# LEMNOS3.net
KiCad netlist of a schematic drawn in EAGLE
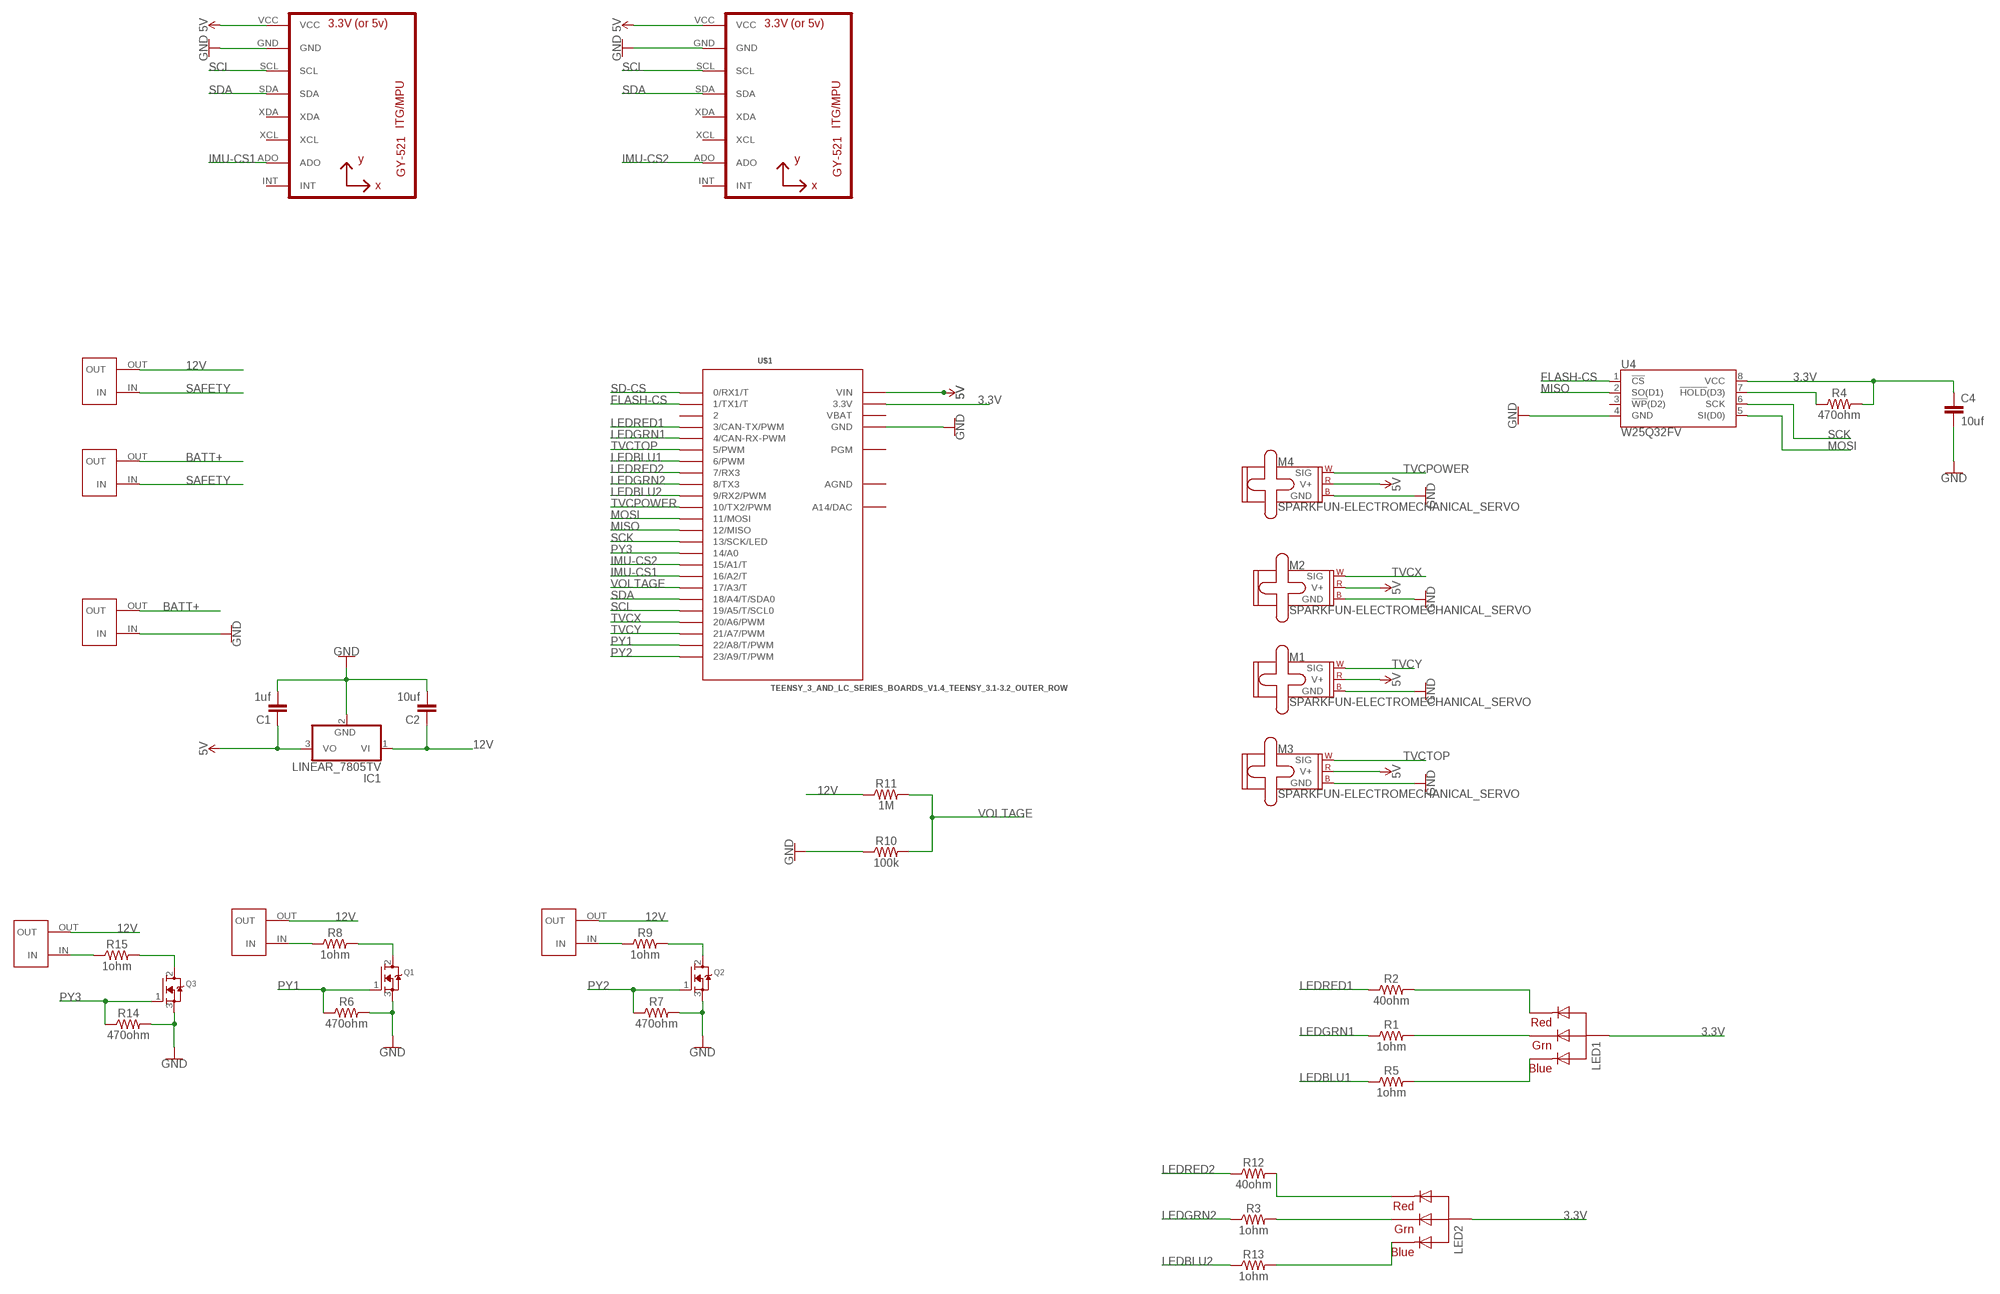
[diagram p0: schematic, sheet 1]

(export (version "E")
  (design (tool "Eeschema 10.0.6"))
  (components
    (comp (ref "C1")
      (value "1uf")
      (footprint "eagle-import:SPARKFUN-CAPACITORS_CAP-PTH-2.54")
      (libsource (lib "eagle-import") (part "SPARKFUN-CAPACITORS_22PF-PTH-2.54MM-200V-5%"))
    )
    (comp (ref "C2")
      (value "10uf")
      (footprint "eagle-import:SPARKFUN-CAPACITORS_CAP-PTH-2.54")
      (libsource (lib "eagle-import") (part "SPARKFUN-CAPACITORS_22PF-PTH-2.54MM-200V-5%"))
    )
    (comp (ref "C4")
      (value "10uf")
      (footprint "eagle-import:SPARKFUN-CAPACITORS_CAP-PTH-2.54")
      (libsource (lib "eagle-import") (part "SPARKFUN-CAPACITORS_22PF-PTH-2.54MM-200V-5%"))
    )
    (comp (ref "IC1")
      (value "LINEAR_7805TV")
      (footprint "eagle-import:LINEAR_TO220V")
      (libsource (lib "eagle-import") (part "LINEAR_78TV05"))
    )
    (comp (ref "LED1")
      (value "RGBLED_CA-5MM")
      (footprint "eagle-import:LED5MMRGB")
      (libsource (lib "eagle-import") (part "RGBLED_CA-5MM"))
    )
    (comp (ref "LED2")
      (value "RGBLED_CA-5MM")
      (footprint "eagle-import:LED5MMRGB")
      (libsource (lib "eagle-import") (part "RGBLED_CA-5MM"))
    )
    (comp (ref "M1")
      (value "SPARKFUN-ELECTROMECHANICAL_SERVO")
      (footprint "eagle-import:SPARKFUN-ELECTROMECHANICAL_1X03")
      (libsource (lib "eagle-import") (part "SPARKFUN-ELECTROMECHANICAL_SERVO"))
    )
    (comp (ref "M2")
      (value "SPARKFUN-ELECTROMECHANICAL_SERVO")
      (footprint "eagle-import:SPARKFUN-ELECTROMECHANICAL_1X03")
      (libsource (lib "eagle-import") (part "SPARKFUN-ELECTROMECHANICAL_SERVO"))
    )
    (comp (ref "M3")
      (value "SPARKFUN-ELECTROMECHANICAL_SERVO")
      (footprint "eagle-import:SPARKFUN-ELECTROMECHANICAL_1X03")
      (libsource (lib "eagle-import") (part "SPARKFUN-ELECTROMECHANICAL_SERVO"))
    )
    (comp (ref "M4")
      (value "SPARKFUN-ELECTROMECHANICAL_SERVO")
      (footprint "eagle-import:SPARKFUN-ELECTROMECHANICAL_1X03")
      (libsource (lib "eagle-import") (part "SPARKFUN-ELECTROMECHANICAL_SERVO"))
    )
    (comp (ref "Q1")
      (value "ADAFRUIT_MOSFET-NGDS_TO220V")
      (footprint "eagle-import:ADAFRUIT_TO220V")
      (libsource (lib "eagle-import") (part "ADAFRUIT_MOSFET-NGDS_TO220V"))
    )
    (comp (ref "Q2")
      (value "ADAFRUIT_MOSFET-NGDS_TO220V")
      (footprint "eagle-import:ADAFRUIT_TO220V")
      (libsource (lib "eagle-import") (part "ADAFRUIT_MOSFET-NGDS_TO220V"))
    )
    (comp (ref "Q3")
      (value "ADAFRUIT_MOSFET-NGDS_TO220V")
      (footprint "eagle-import:ADAFRUIT_TO220V")
      (libsource (lib "eagle-import") (part "ADAFRUIT_MOSFET-NGDS_TO220V"))
    )
    (comp (ref "R1")
      (value "1ohm")
      (footprint "eagle-import:SPARKFUN-RESISTORS_AXIAL-0.3")
      (libsource (lib "eagle-import") (part "SPARKFUN-RESISTORS_10MOHM-HORIZ-1/4W-5%"))
    )
    (comp (ref "R2")
      (value "40ohm")
      (footprint "eagle-import:SPARKFUN-RESISTORS_AXIAL-0.3")
      (libsource (lib "eagle-import") (part "SPARKFUN-RESISTORS_10MOHM-HORIZ-1/4W-5%"))
    )
    (comp (ref "R3")
      (value "1ohm")
      (footprint "eagle-import:SPARKFUN-RESISTORS_AXIAL-0.3")
      (libsource (lib "eagle-import") (part "SPARKFUN-RESISTORS_10MOHM-HORIZ-1/4W-5%"))
    )
    (comp (ref "R4")
      (value "470ohm")
      (footprint "eagle-import:SPARKFUN-RESISTORS_AXIAL-0.3")
      (libsource (lib "eagle-import") (part "SPARKFUN-RESISTORS_10MOHM-HORIZ-1/4W-5%"))
    )
    (comp (ref "R5")
      (value "1ohm")
      (footprint "eagle-import:SPARKFUN-RESISTORS_AXIAL-0.3")
      (libsource (lib "eagle-import") (part "SPARKFUN-RESISTORS_10MOHM-HORIZ-1/4W-5%"))
    )
    (comp (ref "R6")
      (value "470ohm")
      (footprint "eagle-import:SPARKFUN-RESISTORS_AXIAL-0.3")
      (libsource (lib "eagle-import") (part "SPARKFUN-RESISTORS_10MOHM-HORIZ-1/4W-5%"))
    )
    (comp (ref "R7")
      (value "470ohm")
      (footprint "eagle-import:SPARKFUN-RESISTORS_AXIAL-0.3")
      (libsource (lib "eagle-import") (part "SPARKFUN-RESISTORS_10MOHM-HORIZ-1/4W-5%"))
    )
    (comp (ref "R8")
      (value "1ohm")
      (footprint "eagle-import:SPARKFUN-RESISTORS_AXIAL-0.3")
      (libsource (lib "eagle-import") (part "SPARKFUN-RESISTORS_10MOHM-HORIZ-1/4W-5%"))
    )
    (comp (ref "R9")
      (value "1ohm")
      (footprint "eagle-import:SPARKFUN-RESISTORS_AXIAL-0.3")
      (libsource (lib "eagle-import") (part "SPARKFUN-RESISTORS_10MOHM-HORIZ-1/4W-5%"))
    )
    (comp (ref "R10")
      (value "100k")
      (footprint "eagle-import:SPARKFUN-RESISTORS_AXIAL-0.3")
      (libsource (lib "eagle-import") (part "SPARKFUN-RESISTORS_10MOHM-HORIZ-1/4W-5%"))
    )
    (comp (ref "R11")
      (value "1M")
      (footprint "eagle-import:SPARKFUN-RESISTORS_AXIAL-0.3")
      (libsource (lib "eagle-import") (part "SPARKFUN-RESISTORS_10MOHM-HORIZ-1/4W-5%"))
    )
    (comp (ref "R12")
      (value "40ohm")
      (footprint "eagle-import:SPARKFUN-RESISTORS_AXIAL-0.3")
      (libsource (lib "eagle-import") (part "SPARKFUN-RESISTORS_10MOHM-HORIZ-1/4W-5%"))
    )
    (comp (ref "R13")
      (value "1ohm")
      (footprint "eagle-import:SPARKFUN-RESISTORS_AXIAL-0.3")
      (libsource (lib "eagle-import") (part "SPARKFUN-RESISTORS_10MOHM-HORIZ-1/4W-5%"))
    )
    (comp (ref "R14")
      (value "470ohm")
      (footprint "eagle-import:SPARKFUN-RESISTORS_AXIAL-0.3")
      (libsource (lib "eagle-import") (part "SPARKFUN-RESISTORS_10MOHM-HORIZ-1/4W-5%"))
    )
    (comp (ref "R15")
      (value "1ohm")
      (footprint "eagle-import:SPARKFUN-RESISTORS_AXIAL-0.3")
      (libsource (lib "eagle-import") (part "SPARKFUN-RESISTORS_10MOHM-HORIZ-1/4W-5%"))
    )
    (comp (ref "U$1")
      (value "TEENSY_3_AND_LC_SERIES_BOARDS_V1.4_TEENSY_3.1-3.2_OUTER_ROW")
      (footprint "eagle-import:TEENSY_3_AND_LC_SERIES_BOARDS_V1.4_TEENSY_3.0-3.2&LC_OUTER_ROW")
      (libsource (lib "eagle-import") (part "TEENSY_3_AND_LC_SERIES_BOARDS_V1.4_TEENSY_3.1-3.2_OUTER_ROW"))
    )
    (comp (ref "U$2")
      (value "BLACKTERMBLOCK_BLACKTERMBLOCK")
      (footprint "eagle-import:BLACKTERMBLOCK_BLACKTERMBLOCK")
      (libsource (lib "eagle-import") (part "BLACKTERMBLOCK_BLACKTERMBLOCK"))
    )
    (comp (ref "U$3")
      (value "BLACKTERMBLOCK_BLACKTERMBLOCK")
      (footprint "eagle-import:BLACKTERMBLOCK_BLACKTERMBLOCK")
      (libsource (lib "eagle-import") (part "BLACKTERMBLOCK_BLACKTERMBLOCK"))
    )
    (comp (ref "U$4")
      (value "BLACKTERMBLOCK_BLACKTERMBLOCK")
      (footprint "eagle-import:BLACKTERMBLOCK_BLACKTERMBLOCK")
      (libsource (lib "eagle-import") (part "BLACKTERMBLOCK_BLACKTERMBLOCK"))
    )
    (comp (ref "U$5")
      (value "BLACKTERMBLOCK_BLACKTERMBLOCK")
      (footprint "eagle-import:BLACKTERMBLOCK_BLACKTERMBLOCK")
      (libsource (lib "eagle-import") (part "BLACKTERMBLOCK_BLACKTERMBLOCK"))
    )
    (comp (ref "U$6")
      (value "BLACKTERMBLOCK_BLACKTERMBLOCK")
      (footprint "eagle-import:BLACKTERMBLOCK_BLACKTERMBLOCK")
      (libsource (lib "eagle-import") (part "BLACKTERMBLOCK_BLACKTERMBLOCK"))
    )
    (comp (ref "U$8")
      (value "BLACKTERMBLOCK_BLACKTERMBLOCK")
      (footprint "eagle-import:BLACKTERMBLOCK_BLACKTERMBLOCK")
      (libsource (lib "eagle-import") (part "BLACKTERMBLOCK_BLACKTERMBLOCK"))
    )
    (comp (ref "U1")
      (value "GY-521_GY-521MPU6050")
      (footprint "eagle-import:GY-521_GY-521")
      (libsource (lib "eagle-import") (part "GY-521_GY-521MPU6050"))
    )
    (comp (ref "U2")
      (value "GY-521_GY-521MPU6050")
      (footprint "eagle-import:GY-521_GY-521")
      (libsource (lib "eagle-import") (part "GY-521_GY-521MPU6050"))
    )
    (comp (ref "U4")
      (value "W25Q32FV")
      (footprint "eagle-import:SPARKFUN-IC-MEMORY_SOIC-8")
      (libsource (lib "eagle-import") (part "SPARKFUN-IC-MEMORY_W25Q32FVSS"))
    )
  )
  (nets
    (net (code "1") (name "/3.3V") (class "Default")
      (node (ref "C4") (pin "1") (pinfunction "1_1") (pintype "passive"))
      (node (ref "LED1") (pin "2") (pinfunction "VCC_2") (pintype "bidirectional"))
      (node (ref "LED2") (pin "2") (pinfunction "VCC_2") (pintype "bidirectional"))
      (node (ref "R4") (pin "P$2") (pinfunction "2_P$2") (pintype "passive"))
      (node (ref "U$1") (pin "3.3V") (pinfunction "3.3V_3.3V") (pintype "power_in"))
      (node (ref "U$1") (pin "3.3V1") (pinfunction "3.3V_3.3V1") (pintype "power_in"))
      (node (ref "U4") (pin "8") (pinfunction "VCC_8") (pintype "bidirectional"))
    )
    (net (code "2") (name "/12V") (class "Default")
      (node (ref "C2") (pin "1") (pinfunction "1_1") (pintype "passive"))
      (node (ref "IC1") (pin "1") (pinfunction "VI_1") (pintype "input"))
      (node (ref "R11") (pin "P$1") (pinfunction "1_P$1") (pintype "passive"))
      (node (ref "U$2") (pin "OUT") (pinfunction "OUT_OUT") (pintype "bidirectional"))
      (node (ref "U$5") (pin "OUT") (pinfunction "OUT_OUT") (pintype "bidirectional"))
      (node (ref "U$6") (pin "OUT") (pinfunction "OUT_OUT") (pintype "bidirectional"))
      (node (ref "U$8") (pin "OUT") (pinfunction "OUT_OUT") (pintype "bidirectional"))
    )
    (net (code "3") (name "/AGND") (class "Default")
      (node (ref "U$1") (pin "AGND") (pinfunction "AGND_AGND") (pintype "power_in"))
    )
    (net (code "4") (name "/BATT+") (class "Default")
      (node (ref "U$3") (pin "OUT") (pinfunction "OUT_OUT") (pintype "bidirectional"))
      (node (ref "U$4") (pin "OUT") (pinfunction "OUT_OUT") (pintype "bidirectional"))
    )
    (net (code "5") (name "/FLASH-CS") (class "Default")
      (node (ref "U$1") (pin "1") (pinfunction "1/TX1/T_1") (pintype "bidirectional"))
      (node (ref "U4") (pin "1") (pinfunction "~{CS}_1") (pintype "bidirectional"))
    )
    (net (code "6") (name "/IMU-CS1") (class "Default")
      (node (ref "U$1") (pin "16/A2") (pinfunction "16/A2/T_16/A2") (pintype "bidirectional"))
      (node (ref "U1") (pin "ADO") (pinfunction "ADO_ADO") (pintype "bidirectional"))
    )
    (net (code "7") (name "/IMU-CS2") (class "Default")
      (node (ref "U$1") (pin "15/A1") (pinfunction "15/A1/T_15/A1") (pintype "bidirectional"))
      (node (ref "U2") (pin "ADO") (pinfunction "ADO_ADO") (pintype "bidirectional"))
    )
    (net (code "8") (name "/LEDBLU1") (class "Default")
      (node (ref "R5") (pin "P$1") (pinfunction "1_P$1") (pintype "passive"))
      (node (ref "U$1") (pin "6") (pinfunction "6/PWM_6") (pintype "bidirectional"))
    )
    (net (code "9") (name "/LEDBLU2") (class "Default")
      (node (ref "R13") (pin "P$1") (pinfunction "1_P$1") (pintype "passive"))
      (node (ref "U$1") (pin "9") (pinfunction "9/RX2/PWM_9") (pintype "bidirectional"))
    )
    (net (code "10") (name "/LEDGRN1") (class "Default")
      (node (ref "R1") (pin "P$1") (pinfunction "1_P$1") (pintype "passive"))
      (node (ref "U$1") (pin "4") (pinfunction "4/CAN-RX-PWM_4") (pintype "bidirectional"))
    )
    (net (code "11") (name "/LEDGRN2") (class "Default")
      (node (ref "R3") (pin "P$1") (pinfunction "1_P$1") (pintype "passive"))
      (node (ref "U$1") (pin "8") (pinfunction "8/TX3_8") (pintype "bidirectional"))
    )
    (net (code "12") (name "/LEDRED1") (class "Default")
      (node (ref "R2") (pin "P$1") (pinfunction "1_P$1") (pintype "passive"))
      (node (ref "U$1") (pin "3") (pinfunction "3/CAN-TX/PWM_3") (pintype "bidirectional"))
    )
    (net (code "13") (name "/LEDRED2") (class "Default")
      (node (ref "R12") (pin "P$1") (pinfunction "1_P$1") (pintype "passive"))
      (node (ref "U$1") (pin "7") (pinfunction "7/RX3_7") (pintype "bidirectional"))
    )
    (net (code "14") (name "/MISO") (class "Default")
      (node (ref "U$1") (pin "12") (pinfunction "12/MISO_12") (pintype "bidirectional"))
      (node (ref "U4") (pin "2") (pinfunction "SO(D1)_2") (pintype "bidirectional"))
    )
    (net (code "15") (name "/MOSI") (class "Default")
      (node (ref "U$1") (pin "11") (pinfunction "11/MOSI_11") (pintype "bidirectional"))
      (node (ref "U4") (pin "5") (pinfunction "SI(D0)_5") (pintype "bidirectional"))
    )
    (net (code "16") (name "/PY1") (class "Default")
      (node (ref "Q1") (pin "1") (pinfunction "G_1") (pintype "bidirectional"))
      (node (ref "R6") (pin "P$1") (pinfunction "1_P$1") (pintype "passive"))
      (node (ref "U$1") (pin "22/A8") (pinfunction "22/A8/T/PWM_22/A8") (pintype "bidirectional"))
    )
    (net (code "17") (name "/PY2") (class "Default")
      (node (ref "Q2") (pin "1") (pinfunction "G_1") (pintype "bidirectional"))
      (node (ref "R7") (pin "P$1") (pinfunction "1_P$1") (pintype "passive"))
      (node (ref "U$1") (pin "23/A9") (pinfunction "23/A9/T/PWM_23/A9") (pintype "bidirectional"))
    )
    (net (code "18") (name "/PY3") (class "Default")
      (node (ref "Q3") (pin "1") (pinfunction "G_1") (pintype "bidirectional"))
      (node (ref "R14") (pin "P$1") (pinfunction "1_P$1") (pintype "passive"))
      (node (ref "U$1") (pin "14/A0") (pinfunction "14/A0_14/A0") (pintype "bidirectional"))
    )
    (net (code "19") (name "/SAFETY") (class "Default")
      (node (ref "U$4") (pin "IN") (pinfunction "IN_IN") (pintype "bidirectional"))
      (node (ref "U$8") (pin "IN") (pinfunction "IN_IN") (pintype "bidirectional"))
    )
    (net (code "20") (name "/SCK") (class "Default")
      (node (ref "U$1") (pin "13") (pinfunction "13/SCK/LED_13") (pintype "bidirectional"))
      (node (ref "U4") (pin "6") (pinfunction "SCK_6") (pintype "bidirectional"))
    )
    (net (code "21") (name "/SCL") (class "Default")
      (node (ref "U$1") (pin "19/A5") (pinfunction "19/A5/T/SCL0_19/A5") (pintype "bidirectional"))
      (node (ref "U1") (pin "SCL") (pinfunction "SCL_SCL") (pintype "bidirectional"))
      (node (ref "U2") (pin "SCL") (pinfunction "SCL_SCL") (pintype "bidirectional"))
    )
    (net (code "22") (name "/SD-CS") (class "Default")
      (node (ref "U$1") (pin "0") (pinfunction "0/RX1/T_0") (pintype "bidirectional"))
    )
    (net (code "23") (name "/SDA") (class "Default")
      (node (ref "U$1") (pin "18/A4") (pinfunction "18/A4/T/SDA0_18/A4") (pintype "bidirectional"))
      (node (ref "U1") (pin "SDA") (pinfunction "SDA_SDA") (pintype "bidirectional"))
      (node (ref "U2") (pin "SDA") (pinfunction "SDA_SDA") (pintype "bidirectional"))
    )
    (net (code "24") (name "/TVCPOWER") (class "Default")
      (node (ref "M4") (pin "1") (pinfunction "SIG_1") (pintype "bidirectional"))
      (node (ref "U$1") (pin "10") (pinfunction "10/TX2/PWM_10") (pintype "bidirectional"))
    )
    (net (code "25") (name "/TVCTOP") (class "Default")
      (node (ref "M3") (pin "1") (pinfunction "SIG_1") (pintype "bidirectional"))
      (node (ref "U$1") (pin "5") (pinfunction "5/PWM_5") (pintype "bidirectional"))
    )
    (net (code "26") (name "/TVCX") (class "Default")
      (node (ref "M2") (pin "1") (pinfunction "SIG_1") (pintype "bidirectional"))
      (node (ref "U$1") (pin "20/A6") (pinfunction "20/A6/PWM_20/A6") (pintype "bidirectional"))
    )
    (net (code "27") (name "/TVCY") (class "Default")
      (node (ref "M1") (pin "1") (pinfunction "SIG_1") (pintype "bidirectional"))
      (node (ref "U$1") (pin "21/A7") (pinfunction "21/A7/PWM_21/A7") (pintype "bidirectional"))
    )
    (net (code "28") (name "/VBAT") (class "Default")
      (node (ref "U$1") (pin "VBAT") (pinfunction "VBAT_VBAT") (pintype "power_in"))
    )
    (net (code "29") (name "/VOLTAGE") (class "Default")
      (node (ref "R10") (pin "P$2") (pinfunction "2_P$2") (pintype "passive"))
      (node (ref "R11") (pin "P$2") (pinfunction "2_P$2") (pintype "passive"))
      (node (ref "U$1") (pin "17/A3") (pinfunction "17/A3/T_17/A3") (pintype "bidirectional"))
    )
    (net (code "30") (name "5V") (class "Default")
      (node (ref "C1") (pin "1") (pinfunction "1_1") (pintype "passive"))
      (node (ref "IC1") (pin "3") (pinfunction "VO_3") (pintype "passive"))
      (node (ref "M1") (pin "2") (pinfunction "V+_2") (pintype "bidirectional"))
      (node (ref "M2") (pin "2") (pinfunction "V+_2") (pintype "bidirectional"))
      (node (ref "M3") (pin "2") (pinfunction "V+_2") (pintype "bidirectional"))
      (node (ref "M4") (pin "2") (pinfunction "V+_2") (pintype "bidirectional"))
      (node (ref "U$1") (pin "VIN") (pinfunction "VIN_VIN") (pintype "power_in"))
      (node (ref "U1") (pin "VCC") (pinfunction "VCC_VCC") (pintype "bidirectional"))
      (node (ref "U2") (pin "VCC") (pinfunction "VCC_VCC") (pintype "bidirectional"))
    )
    (net (code "31") (name "GND") (class "Default")
      (node (ref "C1") (pin "2") (pinfunction "2_2") (pintype "passive"))
      (node (ref "C2") (pin "2") (pinfunction "2_2") (pintype "passive"))
      (node (ref "C4") (pin "2") (pinfunction "2_2") (pintype "passive"))
      (node (ref "IC1") (pin "2") (pinfunction "GND_2") (pintype "passive"))
      (node (ref "M1") (pin "3") (pinfunction "GND_3") (pintype "bidirectional"))
      (node (ref "M2") (pin "3") (pinfunction "GND_3") (pintype "bidirectional"))
      (node (ref "M3") (pin "3") (pinfunction "GND_3") (pintype "bidirectional"))
      (node (ref "M4") (pin "3") (pinfunction "GND_3") (pintype "bidirectional"))
      (node (ref "Q1") (pin "3") (pinfunction "S_3") (pintype "bidirectional"))
      (node (ref "Q2") (pin "3") (pinfunction "S_3") (pintype "bidirectional"))
      (node (ref "Q3") (pin "3") (pinfunction "S_3") (pintype "bidirectional"))
      (node (ref "R10") (pin "P$1") (pinfunction "1_P$1") (pintype "passive"))
      (node (ref "R14") (pin "P$2") (pinfunction "2_P$2") (pintype "passive"))
      (node (ref "R6") (pin "P$2") (pinfunction "2_P$2") (pintype "passive"))
      (node (ref "R7") (pin "P$2") (pinfunction "2_P$2") (pintype "passive"))
      (node (ref "U$1") (pin "GND") (pinfunction "GND_GND") (pintype "power_in"))
      (node (ref "U$1") (pin "GND1") (pinfunction "GND_GND1") (pintype "power_in"))
      (node (ref "U$3") (pin "IN") (pinfunction "IN_IN") (pintype "bidirectional"))
      (node (ref "U1") (pin "GND") (pinfunction "GND_GND") (pintype "bidirectional"))
      (node (ref "U2") (pin "GND") (pinfunction "GND_GND") (pintype "bidirectional"))
      (node (ref "U4") (pin "4") (pinfunction "GND_4") (pintype "bidirectional"))
    )
    (net (code "32") (name "Net-(LED1-BLUE)") (class "Default")
      (node (ref "LED1") (pin "4") (pinfunction "BLUE_4") (pintype "bidirectional"))
      (node (ref "R5") (pin "P$2") (pinfunction "2_P$2") (pintype "passive"))
    )
    (net (code "33") (name "Net-(LED1-GREEN)") (class "Default")
      (node (ref "LED1") (pin "3") (pinfunction "GREEN_3") (pintype "bidirectional"))
      (node (ref "R1") (pin "P$2") (pinfunction "2_P$2") (pintype "passive"))
    )
    (net (code "34") (name "Net-(LED1-RED)") (class "Default")
      (node (ref "LED1") (pin "1") (pinfunction "RED_1") (pintype "bidirectional"))
      (node (ref "R2") (pin "P$2") (pinfunction "2_P$2") (pintype "passive"))
    )
    (net (code "35") (name "Net-(LED2-BLUE)") (class "Default")
      (node (ref "LED2") (pin "4") (pinfunction "BLUE_4") (pintype "bidirectional"))
      (node (ref "R13") (pin "P$2") (pinfunction "2_P$2") (pintype "passive"))
    )
    (net (code "36") (name "Net-(LED2-GREEN)") (class "Default")
      (node (ref "LED2") (pin "3") (pinfunction "GREEN_3") (pintype "bidirectional"))
      (node (ref "R3") (pin "P$2") (pinfunction "2_P$2") (pintype "passive"))
    )
    (net (code "37") (name "Net-(LED2-RED)") (class "Default")
      (node (ref "LED2") (pin "1") (pinfunction "RED_1") (pintype "bidirectional"))
      (node (ref "R12") (pin "P$2") (pinfunction "2_P$2") (pintype "passive"))
    )
    (net (code "38") (name "Net-(Q1-D)") (class "Default")
      (node (ref "Q1") (pin "2") (pinfunction "D_2") (pintype "bidirectional"))
      (node (ref "R8") (pin "P$2") (pinfunction "2_P$2") (pintype "passive"))
    )
    (net (code "39") (name "Net-(Q2-D)") (class "Default")
      (node (ref "Q2") (pin "2") (pinfunction "D_2") (pintype "bidirectional"))
      (node (ref "R9") (pin "P$2") (pinfunction "2_P$2") (pintype "passive"))
    )
    (net (code "40") (name "Net-(Q3-D)") (class "Default")
      (node (ref "Q3") (pin "2") (pinfunction "D_2") (pintype "bidirectional"))
      (node (ref "R15") (pin "P$2") (pinfunction "2_P$2") (pintype "passive"))
    )
    (net (code "41") (name "Net-(R4-1)") (class "Default")
      (node (ref "R4") (pin "P$1") (pinfunction "1_P$1") (pintype "passive"))
      (node (ref "U4") (pin "7") (pinfunction "~{HOLD}(D3)_7") (pintype "bidirectional"))
    )
    (net (code "42") (name "Net-(R8-1)") (class "Default")
      (node (ref "R8") (pin "P$1") (pinfunction "1_P$1") (pintype "passive"))
      (node (ref "U$5") (pin "IN") (pinfunction "IN_IN") (pintype "bidirectional"))
    )
    (net (code "43") (name "Net-(R9-1)") (class "Default")
      (node (ref "R9") (pin "P$1") (pinfunction "1_P$1") (pintype "passive"))
      (node (ref "U$6") (pin "IN") (pinfunction "IN_IN") (pintype "bidirectional"))
    )
    (net (code "44") (name "Net-(R15-1)") (class "Default")
      (node (ref "R15") (pin "P$1") (pinfunction "1_P$1") (pintype "passive"))
      (node (ref "U$2") (pin "IN") (pinfunction "IN_IN") (pintype "bidirectional"))
    )
    (net (code "45") (name "unconnected-(U$1-A14{slash}DAC-PadRESET{slash}DAC)") (class "Default")
      (node (ref "U$1") (pin "RESET/DAC") (pinfunction "A14/DAC_RESET/DAC") (pintype "bidirectional"))
    )
    (net (code "46") (name "unconnected-(U$1-Pad2)") (class "Default")
      (node (ref "U$1") (pin "2") (pinfunction "2_2") (pintype "bidirectional"))
    )
    (net (code "47") (name "unconnected-(U$1-PadPGM)") (class "Default")
      (node (ref "U$1") (pin "PGM") (pinfunction "PGM_PGM") (pintype "bidirectional"))
    )
    (net (code "48") (name "unconnected-(U1-PadINT)") (class "Default")
      (node (ref "U1") (pin "INT") (pinfunction "INT_INT") (pintype "bidirectional"))
    )
    (net (code "49") (name "unconnected-(U1-PadXCL)") (class "Default")
      (node (ref "U1") (pin "XCL") (pinfunction "XCL_XCL") (pintype "bidirectional"))
    )
    (net (code "50") (name "unconnected-(U1-PadXDA)") (class "Default")
      (node (ref "U1") (pin "XDA") (pinfunction "XDA_XDA") (pintype "bidirectional"))
    )
    (net (code "51") (name "unconnected-(U2-PadINT)") (class "Default")
      (node (ref "U2") (pin "INT") (pinfunction "INT_INT") (pintype "bidirectional"))
    )
    (net (code "52") (name "unconnected-(U2-PadXCL)") (class "Default")
      (node (ref "U2") (pin "XCL") (pinfunction "XCL_XCL") (pintype "bidirectional"))
    )
    (net (code "53") (name "unconnected-(U2-PadXDA)") (class "Default")
      (node (ref "U2") (pin "XDA") (pinfunction "XDA_XDA") (pintype "bidirectional"))
    )
    (net (code "54") (name "unconnected-(U4-~{WP}(D2)-Pad3)") (class "Default")
      (node (ref "U4") (pin "3") (pinfunction "~{WP}(D2)_3") (pintype "bidirectional"))
    )
  )
)
